# schematic.net
KiCad netlist of a schematic drawn in EAGLE
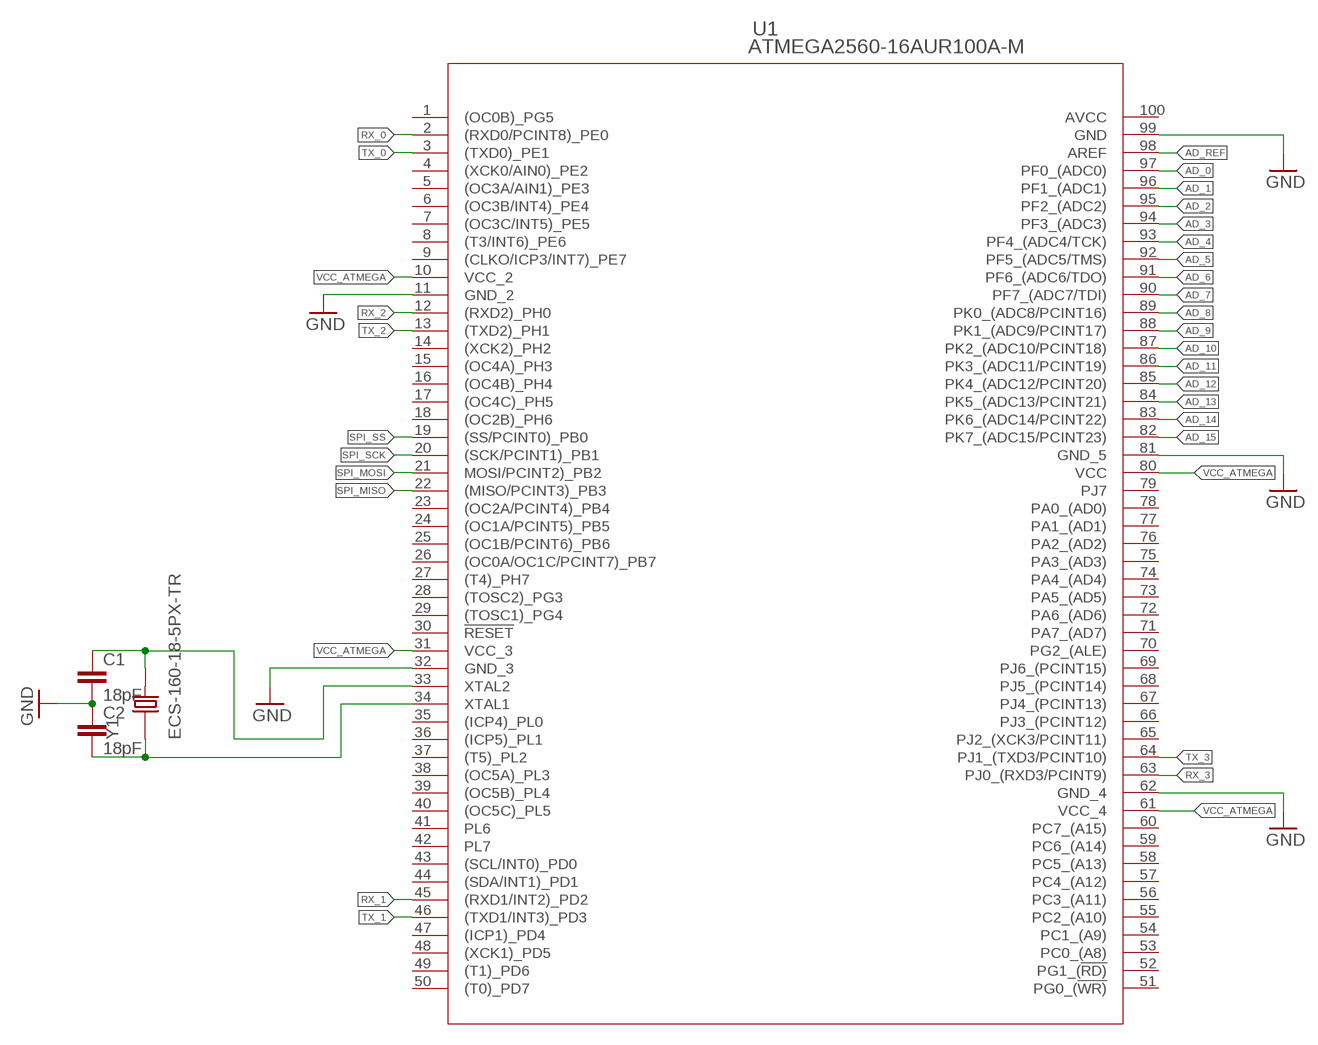
[diagram p0: schematic, sheet 1]

(export (version "E")
  (design (tool "Eeschema 10.0.6"))
  (components
    (comp (ref "C1")
      (value "18pF")
      (footprint "eagle-import:C0603")
      (libsource (lib "eagle-import") (part "C-EUC0603"))
    )
    (comp (ref "C2")
      (value "18pF")
      (footprint "eagle-import:C0603")
      (libsource (lib "eagle-import") (part "C-EUC0603"))
    )
    (comp (ref "U1")
      (value "ATMEGA2560-16AUR100A-M")
      (footprint "eagle-import:100A-M")
      (fields (field (name "MANUFACTURER_PART_NUMBER") "ATMEGA256016AUR"))
      (libsource (lib "eagle-import") (part "ATMEGA2560-16AUR100A-M"))
    )
    (comp (ref "Y1")
      (value "ECS-160-18-5PX-TR")
      (footprint "eagle-import:XTAL_ECS-160-18-5PX-TR")
      (fields (field (name "DIGI-KEY_PART_NUMBER") "XC2081CT-ND") (field (name "MF") "ECS Inc."))
      (libsource (lib "eagle-import") (part "ECS-160-18-5PX-TR"))
    )
  )
  (nets
    (net (code "1") (name "AD_0") (class "Default")
      (node (ref "U1") (pin "97") (pinfunction "PF0_(ADC0)_97") (pintype "bidirectional"))
    )
    (net (code "2") (name "AD_1") (class "Default")
      (node (ref "U1") (pin "96") (pinfunction "PF1_(ADC1)_96") (pintype "bidirectional"))
    )
    (net (code "3") (name "AD_2") (class "Default")
      (node (ref "U1") (pin "95") (pinfunction "PF2_(ADC2)_95") (pintype "bidirectional"))
    )
    (net (code "4") (name "AD_3") (class "Default")
      (node (ref "U1") (pin "94") (pinfunction "PF3_(ADC3)_94") (pintype "passive"))
    )
    (net (code "5") (name "AD_4") (class "Default")
      (node (ref "U1") (pin "93") (pinfunction "PF4_(ADC4/TCK)_93") (pintype "power_in"))
    )
    (net (code "6") (name "AD_5") (class "Default")
      (node (ref "U1") (pin "92") (pinfunction "PF5_(ADC5/TMS)_92") (pintype "power_in"))
    )
    (net (code "7") (name "AD_6") (class "Default")
      (node (ref "U1") (pin "91") (pinfunction "PF6_(ADC6/TDO)_91") (pintype "bidirectional"))
    )
    (net (code "8") (name "AD_7") (class "Default")
      (node (ref "U1") (pin "90") (pinfunction "PF7_(ADC7/TDI)_90") (pintype "bidirectional"))
    )
    (net (code "9") (name "AD_8") (class "Default")
      (node (ref "U1") (pin "89") (pinfunction "PK0_(ADC8/PCINT16)_89") (pintype "bidirectional"))
    )
    (net (code "10") (name "AD_9") (class "Default")
      (node (ref "U1") (pin "88") (pinfunction "PK1_(ADC9/PCINT17)_88") (pintype "bidirectional"))
    )
    (net (code "11") (name "AD_10") (class "Default")
      (node (ref "U1") (pin "87") (pinfunction "PK2_(ADC10/PCINT18)_87") (pintype "bidirectional"))
    )
    (net (code "12") (name "AD_11") (class "Default")
      (node (ref "U1") (pin "86") (pinfunction "PK3_(ADC11/PCINT19)_86") (pintype "bidirectional"))
    )
    (net (code "13") (name "AD_12") (class "Default")
      (node (ref "U1") (pin "85") (pinfunction "PK4_(ADC12/PCINT20)_85") (pintype "bidirectional"))
    )
    (net (code "14") (name "AD_13") (class "Default")
      (node (ref "U1") (pin "84") (pinfunction "PK5_(ADC13/PCINT21)_84") (pintype "bidirectional"))
    )
    (net (code "15") (name "AD_14") (class "Default")
      (node (ref "U1") (pin "83") (pinfunction "PK6_(ADC14/PCINT22)_83") (pintype "bidirectional"))
    )
    (net (code "16") (name "AD_15") (class "Default")
      (node (ref "U1") (pin "82") (pinfunction "PK7_(ADC15/PCINT23)_82") (pintype "bidirectional"))
    )
    (net (code "17") (name "AD_REF") (class "Default")
      (node (ref "U1") (pin "98") (pinfunction "AREF_98") (pintype "bidirectional"))
    )
    (net (code "18") (name "GND") (class "Default")
      (node (ref "C1") (pin "2") (pinfunction "2_2") (pintype "passive"))
      (node (ref "C2") (pin "1") (pinfunction "1_1") (pintype "passive"))
      (node (ref "U1") (pin "11") (pinfunction "GND_2_11") (pintype "power_in"))
      (node (ref "U1") (pin "32") (pinfunction "GND_3_32") (pintype "power_in"))
      (node (ref "U1") (pin "62") (pinfunction "GND_4_62") (pintype "power_in"))
      (node (ref "U1") (pin "81") (pinfunction "GND_5_81") (pintype "power_in"))
      (node (ref "U1") (pin "99") (pinfunction "GND_99") (pintype "bidirectional"))
    )
    (net (code "19") (name "Net-(U1-XTAL1)") (class "Default")
      (node (ref "C2") (pin "2") (pinfunction "2_2") (pintype "passive"))
      (node (ref "U1") (pin "34") (pinfunction "XTAL1_34") (pintype "input"))
      (node (ref "Y1") (pin "1") (pinfunction "1_1") (pintype "passive"))
    )
    (net (code "20") (name "Net-(U1-XTAL2)") (class "Default")
      (node (ref "C1") (pin "1") (pinfunction "1_1") (pintype "passive"))
      (node (ref "U1") (pin "33") (pinfunction "XTAL2_33") (pintype "output"))
      (node (ref "Y1") (pin "2") (pinfunction "2_2") (pintype "passive"))
    )
    (net (code "21") (name "RX_0") (class "Default")
      (node (ref "U1") (pin "2") (pinfunction "(RXD0/PCINT8)_PE0_2") (pintype "bidirectional"))
    )
    (net (code "22") (name "RX_1") (class "Default")
      (node (ref "U1") (pin "45") (pinfunction "(RXD1/INT2)_PD2_45") (pintype "bidirectional"))
    )
    (net (code "23") (name "RX_2") (class "Default")
      (node (ref "U1") (pin "12") (pinfunction "(RXD2)_PH0_12") (pintype "bidirectional"))
    )
    (net (code "24") (name "RX_3") (class "Default")
      (node (ref "U1") (pin "63") (pinfunction "PJ0_(RXD3/PCINT9)_63") (pintype "bidirectional"))
    )
    (net (code "25") (name "SPI_MISO") (class "Default")
      (node (ref "U1") (pin "22") (pinfunction "(MISO/PCINT3)_PB3_22") (pintype "bidirectional"))
    )
    (net (code "26") (name "SPI_MOSI") (class "Default")
      (node (ref "U1") (pin "21") (pinfunction "MOSI/PCINT2)_PB2_21") (pintype "bidirectional"))
    )
    (net (code "27") (name "SPI_SCK") (class "Default")
      (node (ref "U1") (pin "20") (pinfunction "(SCK/PCINT1)_PB1_20") (pintype "bidirectional"))
    )
    (net (code "28") (name "SPI_SS") (class "Default")
      (node (ref "U1") (pin "19") (pinfunction "(SS/PCINT0)_PB0_19") (pintype "bidirectional"))
    )
    (net (code "29") (name "TX_0") (class "Default")
      (node (ref "U1") (pin "3") (pinfunction "(TXD0)_PE1_3") (pintype "bidirectional"))
    )
    (net (code "30") (name "TX_1") (class "Default")
      (node (ref "U1") (pin "46") (pinfunction "(TXD1/INT3)_PD3_46") (pintype "bidirectional"))
    )
    (net (code "31") (name "TX_2") (class "Default")
      (node (ref "U1") (pin "13") (pinfunction "(TXD2)_PH1_13") (pintype "bidirectional"))
    )
    (net (code "32") (name "TX_3") (class "Default")
      (node (ref "U1") (pin "64") (pinfunction "PJ1_(TXD3/PCINT10)_64") (pintype "bidirectional"))
    )
    (net (code "33") (name "VCC_ATMEGA") (class "Default")
      (node (ref "U1") (pin "10") (pinfunction "VCC_2_10") (pintype "power_in"))
      (node (ref "U1") (pin "31") (pinfunction "VCC_3_31") (pintype "power_in"))
      (node (ref "U1") (pin "61") (pinfunction "VCC_4_61") (pintype "power_in"))
      (node (ref "U1") (pin "80") (pinfunction "VCC_80") (pintype "power_in"))
    )
    (net (code "34") (name "unconnected-(U1-(CLKO{slash}ICP3{slash}INT7)_PE7-Pad9)") (class "Default")
      (node (ref "U1") (pin "9") (pinfunction "(CLKO/ICP3/INT7)_PE7_9") (pintype "bidirectional"))
    )
    (net (code "35") (name "unconnected-(U1-(ICP1)_PD4-Pad47)") (class "Default")
      (node (ref "U1") (pin "47") (pinfunction "(ICP1)_PD4_47") (pintype "bidirectional"))
    )
    (net (code "36") (name "unconnected-(U1-(ICP4)_PL0-Pad35)") (class "Default")
      (node (ref "U1") (pin "35") (pinfunction "(ICP4)_PL0_35") (pintype "bidirectional"))
    )
    (net (code "37") (name "unconnected-(U1-(ICP5)_PL1-Pad36)") (class "Default")
      (node (ref "U1") (pin "36") (pinfunction "(ICP5)_PL1_36") (pintype "bidirectional"))
    )
    (net (code "38") (name "unconnected-(U1-(OC0A{slash}OC1C{slash}PCINT7)_PB7-Pad26)") (class "Default")
      (node (ref "U1") (pin "26") (pinfunction "(OC0A/OC1C/PCINT7)_PB7_26") (pintype "bidirectional"))
    )
    (net (code "39") (name "unconnected-(U1-(OC0B)_PG5-Pad1)") (class "Default")
      (node (ref "U1") (pin "1") (pinfunction "(OC0B)_PG5_1") (pintype "bidirectional"))
    )
    (net (code "40") (name "unconnected-(U1-(OC1A{slash}PCINT5)_PB5-Pad24)") (class "Default")
      (node (ref "U1") (pin "24") (pinfunction "(OC1A/PCINT5)_PB5_24") (pintype "bidirectional"))
    )
    (net (code "41") (name "unconnected-(U1-(OC1B{slash}PCINT6)_PB6-Pad25)") (class "Default")
      (node (ref "U1") (pin "25") (pinfunction "(OC1B/PCINT6)_PB6_25") (pintype "bidirectional"))
    )
    (net (code "42") (name "unconnected-(U1-(OC2A{slash}PCINT4)_PB4-Pad23)") (class "Default")
      (node (ref "U1") (pin "23") (pinfunction "(OC2A/PCINT4)_PB4_23") (pintype "bidirectional"))
    )
    (net (code "43") (name "unconnected-(U1-(OC2B)_PH6-Pad18)") (class "Default")
      (node (ref "U1") (pin "18") (pinfunction "(OC2B)_PH6_18") (pintype "bidirectional"))
    )
    (net (code "44") (name "unconnected-(U1-(OC3A{slash}AIN1)_PE3-Pad5)") (class "Default")
      (node (ref "U1") (pin "5") (pinfunction "(OC3A/AIN1)_PE3_5") (pintype "bidirectional"))
    )
    (net (code "45") (name "unconnected-(U1-(OC3B{slash}INT4)_PE4-Pad6)") (class "Default")
      (node (ref "U1") (pin "6") (pinfunction "(OC3B/INT4)_PE4_6") (pintype "bidirectional"))
    )
    (net (code "46") (name "unconnected-(U1-(OC3C{slash}INT5)_PE5-Pad7)") (class "Default")
      (node (ref "U1") (pin "7") (pinfunction "(OC3C/INT5)_PE5_7") (pintype "bidirectional"))
    )
    (net (code "47") (name "unconnected-(U1-(OC4A)_PH3-Pad15)") (class "Default")
      (node (ref "U1") (pin "15") (pinfunction "(OC4A)_PH3_15") (pintype "bidirectional"))
    )
    (net (code "48") (name "unconnected-(U1-(OC4B)_PH4-Pad16)") (class "Default")
      (node (ref "U1") (pin "16") (pinfunction "(OC4B)_PH4_16") (pintype "bidirectional"))
    )
    (net (code "49") (name "unconnected-(U1-(OC4C)_PH5-Pad17)") (class "Default")
      (node (ref "U1") (pin "17") (pinfunction "(OC4C)_PH5_17") (pintype "bidirectional"))
    )
    (net (code "50") (name "unconnected-(U1-(OC5A)_PL3-Pad38)") (class "Default")
      (node (ref "U1") (pin "38") (pinfunction "(OC5A)_PL3_38") (pintype "bidirectional"))
    )
    (net (code "51") (name "unconnected-(U1-(OC5B)_PL4-Pad39)") (class "Default")
      (node (ref "U1") (pin "39") (pinfunction "(OC5B)_PL4_39") (pintype "bidirectional"))
    )
    (net (code "52") (name "unconnected-(U1-(OC5C)_PL5-Pad40)") (class "Default")
      (node (ref "U1") (pin "40") (pinfunction "(OC5C)_PL5_40") (pintype "bidirectional"))
    )
    (net (code "53") (name "unconnected-(U1-(SCL{slash}INT0)_PD0-Pad43)") (class "Default")
      (node (ref "U1") (pin "43") (pinfunction "(SCL/INT0)_PD0_43") (pintype "bidirectional"))
    )
    (net (code "54") (name "unconnected-(U1-(SDA{slash}INT1)_PD1-Pad44)") (class "Default")
      (node (ref "U1") (pin "44") (pinfunction "(SDA/INT1)_PD1_44") (pintype "bidirectional"))
    )
    (net (code "55") (name "unconnected-(U1-(T0)_PD7-Pad50)") (class "Default")
      (node (ref "U1") (pin "50") (pinfunction "(T0)_PD7_50") (pintype "bidirectional"))
    )
    (net (code "56") (name "unconnected-(U1-(T1)_PD6-Pad49)") (class "Default")
      (node (ref "U1") (pin "49") (pinfunction "(T1)_PD6_49") (pintype "bidirectional"))
    )
    (net (code "57") (name "unconnected-(U1-(T3{slash}INT6)_PE6-Pad8)") (class "Default")
      (node (ref "U1") (pin "8") (pinfunction "(T3/INT6)_PE6_8") (pintype "bidirectional"))
    )
    (net (code "58") (name "unconnected-(U1-(T4)_PH7-Pad27)") (class "Default")
      (node (ref "U1") (pin "27") (pinfunction "(T4)_PH7_27") (pintype "bidirectional"))
    )
    (net (code "59") (name "unconnected-(U1-(T5)_PL2-Pad37)") (class "Default")
      (node (ref "U1") (pin "37") (pinfunction "(T5)_PL2_37") (pintype "bidirectional"))
    )
    (net (code "60") (name "unconnected-(U1-(TOSC1)_PG4-Pad29)") (class "Default")
      (node (ref "U1") (pin "29") (pinfunction "(TOSC1)_PG4_29") (pintype "bidirectional"))
    )
    (net (code "61") (name "unconnected-(U1-(TOSC2)_PG3-Pad28)") (class "Default")
      (node (ref "U1") (pin "28") (pinfunction "(TOSC2)_PG3_28") (pintype "bidirectional"))
    )
    (net (code "62") (name "unconnected-(U1-(XCK0{slash}AIN0)_PE2-Pad4)") (class "Default")
      (node (ref "U1") (pin "4") (pinfunction "(XCK0/AIN0)_PE2_4") (pintype "bidirectional"))
    )
    (net (code "63") (name "unconnected-(U1-(XCK1)_PD5-Pad48)") (class "Default")
      (node (ref "U1") (pin "48") (pinfunction "(XCK1)_PD5_48") (pintype "bidirectional"))
    )
    (net (code "64") (name "unconnected-(U1-(XCK2)_PH2-Pad14)") (class "Default")
      (node (ref "U1") (pin "14") (pinfunction "(XCK2)_PH2_14") (pintype "bidirectional"))
    )
    (net (code "65") (name "unconnected-(U1-AVCC-Pad100)") (class "Default")
      (node (ref "U1") (pin "100") (pinfunction "AVCC_100") (pintype "bidirectional"))
    )
    (net (code "66") (name "unconnected-(U1-PA0_(AD0)-Pad78)") (class "Default")
      (node (ref "U1") (pin "78") (pinfunction "PA0_(AD0)_78") (pintype "bidirectional"))
    )
    (net (code "67") (name "unconnected-(U1-PA1_(AD1)-Pad77)") (class "Default")
      (node (ref "U1") (pin "77") (pinfunction "PA1_(AD1)_77") (pintype "bidirectional"))
    )
    (net (code "68") (name "unconnected-(U1-PA2_(AD2)-Pad76)") (class "Default")
      (node (ref "U1") (pin "76") (pinfunction "PA2_(AD2)_76") (pintype "bidirectional"))
    )
    (net (code "69") (name "unconnected-(U1-PA3_(AD3)-Pad75)") (class "Default")
      (node (ref "U1") (pin "75") (pinfunction "PA3_(AD3)_75") (pintype "bidirectional"))
    )
    (net (code "70") (name "unconnected-(U1-PA4_(AD4)-Pad74)") (class "Default")
      (node (ref "U1") (pin "74") (pinfunction "PA4_(AD4)_74") (pintype "bidirectional"))
    )
    (net (code "71") (name "unconnected-(U1-PA5_(AD5)-Pad73)") (class "Default")
      (node (ref "U1") (pin "73") (pinfunction "PA5_(AD5)_73") (pintype "bidirectional"))
    )
    (net (code "72") (name "unconnected-(U1-PA6_(AD6)-Pad72)") (class "Default")
      (node (ref "U1") (pin "72") (pinfunction "PA6_(AD6)_72") (pintype "bidirectional"))
    )
    (net (code "73") (name "unconnected-(U1-PA7_(AD7)-Pad71)") (class "Default")
      (node (ref "U1") (pin "71") (pinfunction "PA7_(AD7)_71") (pintype "bidirectional"))
    )
    (net (code "74") (name "unconnected-(U1-PC0_(A8)-Pad53)") (class "Default")
      (node (ref "U1") (pin "53") (pinfunction "PC0_(A8)_53") (pintype "bidirectional"))
    )
    (net (code "75") (name "unconnected-(U1-PC1_(A9)-Pad54)") (class "Default")
      (node (ref "U1") (pin "54") (pinfunction "PC1_(A9)_54") (pintype "bidirectional"))
    )
    (net (code "76") (name "unconnected-(U1-PC2_(A10)-Pad55)") (class "Default")
      (node (ref "U1") (pin "55") (pinfunction "PC2_(A10)_55") (pintype "bidirectional"))
    )
    (net (code "77") (name "unconnected-(U1-PC3_(A11)-Pad56)") (class "Default")
      (node (ref "U1") (pin "56") (pinfunction "PC3_(A11)_56") (pintype "bidirectional"))
    )
    (net (code "78") (name "unconnected-(U1-PC4_(A12)-Pad57)") (class "Default")
      (node (ref "U1") (pin "57") (pinfunction "PC4_(A12)_57") (pintype "bidirectional"))
    )
    (net (code "79") (name "unconnected-(U1-PC5_(A13)-Pad58)") (class "Default")
      (node (ref "U1") (pin "58") (pinfunction "PC5_(A13)_58") (pintype "bidirectional"))
    )
    (net (code "80") (name "unconnected-(U1-PC6_(A14)-Pad59)") (class "Default")
      (node (ref "U1") (pin "59") (pinfunction "PC6_(A14)_59") (pintype "bidirectional"))
    )
    (net (code "81") (name "unconnected-(U1-PC7_(A15)-Pad60)") (class "Default")
      (node (ref "U1") (pin "60") (pinfunction "PC7_(A15)_60") (pintype "bidirectional"))
    )
    (net (code "82") (name "unconnected-(U1-PG0_(~{WR})-Pad51)") (class "Default")
      (node (ref "U1") (pin "51") (pinfunction "PG0_(~{WR})_51") (pintype "bidirectional"))
    )
    (net (code "83") (name "unconnected-(U1-PG1_(~{RD})-Pad52)") (class "Default")
      (node (ref "U1") (pin "52") (pinfunction "PG1_(~{RD})_52") (pintype "bidirectional"))
    )
    (net (code "84") (name "unconnected-(U1-PG2_(ALE)-Pad70)") (class "Default")
      (node (ref "U1") (pin "70") (pinfunction "PG2_(ALE)_70") (pintype "bidirectional"))
    )
    (net (code "85") (name "unconnected-(U1-PJ2_(XCK3{slash}PCINT11)-Pad65)") (class "Default")
      (node (ref "U1") (pin "65") (pinfunction "PJ2_(XCK3/PCINT11)_65") (pintype "bidirectional"))
    )
    (net (code "86") (name "unconnected-(U1-PJ3_(PCINT12)-Pad66)") (class "Default")
      (node (ref "U1") (pin "66") (pinfunction "PJ3_(PCINT12)_66") (pintype "bidirectional"))
    )
    (net (code "87") (name "unconnected-(U1-PJ4_(PCINT13)-Pad67)") (class "Default")
      (node (ref "U1") (pin "67") (pinfunction "PJ4_(PCINT13)_67") (pintype "bidirectional"))
    )
    (net (code "88") (name "unconnected-(U1-PJ5_(PCINT14)-Pad68)") (class "Default")
      (node (ref "U1") (pin "68") (pinfunction "PJ5_(PCINT14)_68") (pintype "bidirectional"))
    )
    (net (code "89") (name "unconnected-(U1-PJ6_(PCINT15)-Pad69)") (class "Default")
      (node (ref "U1") (pin "69") (pinfunction "PJ6_(PCINT15)_69") (pintype "bidirectional"))
    )
    (net (code "90") (name "unconnected-(U1-PJ7-Pad79)") (class "Default")
      (node (ref "U1") (pin "79") (pinfunction "PJ7_79") (pintype "bidirectional"))
    )
    (net (code "91") (name "unconnected-(U1-PL6-Pad41)") (class "Default")
      (node (ref "U1") (pin "41") (pinfunction "PL6_41") (pintype "bidirectional"))
    )
    (net (code "92") (name "unconnected-(U1-PL7-Pad42)") (class "Default")
      (node (ref "U1") (pin "42") (pinfunction "PL7_42") (pintype "bidirectional"))
    )
    (net (code "93") (name "unconnected-(U1-~{RESET}-Pad30)") (class "Default")
      (node (ref "U1") (pin "30") (pinfunction "~{RESET}_30") (pintype "input"))
    )
  )
)
